# controller_power.net
KiCad netlist of a schematic drawn in Altium Designer
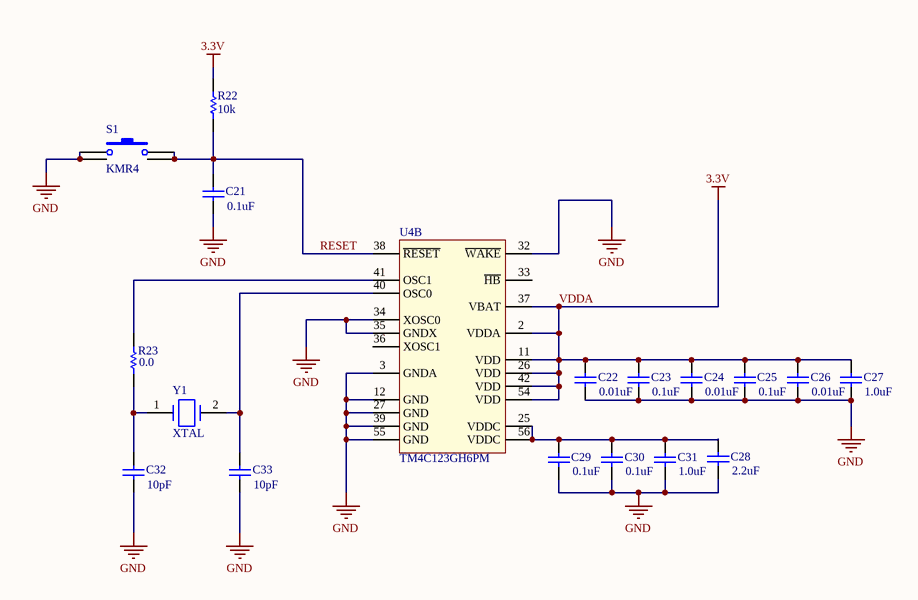
[diagram p0: controller_power.SchDoc]

(export (version "E")
  (design (tool "Eeschema 10.0.6"))
  (components
    (comp (ref "C21")
      (value "0.1uF")
      (footprint "1608[0603]")
      (description "Capacitor (Semiconductor SIM Model)")
      (fields (field (name "Comment") "Cap Semi") (field (name "PUBLISHER") "Altium Limited"))
      (libsource (lib "Miscellaneous Devices") (part "Cap Semi"))
    )
    (comp (ref "C22")
      (value "0.01uF")
      (footprint "1608[0603]")
      (description "Capacitor (Semiconductor SIM Model)")
      (fields (field (name "Comment") "Cap Semi") (field (name "PUBLISHER") "Altium Limited"))
      (libsource (lib "Miscellaneous Devices") (part "Cap Semi"))
    )
    (comp (ref "C23")
      (value "0.1uF")
      (footprint "1608[0603]")
      (description "Capacitor (Semiconductor SIM Model)")
      (fields (field (name "Comment") "Cap Semi") (field (name "PUBLISHER") "Altium Limited"))
      (libsource (lib "Miscellaneous Devices") (part "Cap Semi"))
    )
    (comp (ref "C24")
      (value "0.01uF")
      (footprint "1608[0603]")
      (description "Capacitor (Semiconductor SIM Model)")
      (fields (field (name "Comment") "Cap Semi") (field (name "PUBLISHER") "Altium Limited"))
      (libsource (lib "Miscellaneous Devices") (part "Cap Semi"))
    )
    (comp (ref "C25")
      (value "0.1uF")
      (footprint "1608[0603]")
      (description "Capacitor (Semiconductor SIM Model)")
      (fields (field (name "Comment") "Cap Semi") (field (name "PUBLISHER") "Altium Limited"))
      (libsource (lib "Miscellaneous Devices") (part "Cap Semi"))
    )
    (comp (ref "C26")
      (value "0.01uF")
      (footprint "1608[0603]")
      (description "Capacitor (Semiconductor SIM Model)")
      (fields (field (name "Comment") "Cap Semi") (field (name "PUBLISHER") "Altium Limited"))
      (libsource (lib "Miscellaneous Devices") (part "Cap Semi"))
    )
    (comp (ref "C27")
      (value "1.0uF")
      (footprint "1608[0603]")
      (description "Capacitor (Semiconductor SIM Model)")
      (fields (field (name "Comment") "Cap Semi") (field (name "PUBLISHER") "Altium Limited"))
      (libsource (lib "Miscellaneous Devices") (part "Cap Semi"))
    )
    (comp (ref "C28")
      (value "2.2uF")
      (footprint "1608[0603]")
      (description "Capacitor (Semiconductor SIM Model)")
      (fields (field (name "Comment") "Cap Semi") (field (name "PUBLISHER") "Altium Limited"))
      (libsource (lib "Miscellaneous Devices") (part "Cap Semi"))
    )
    (comp (ref "C29")
      (value "0.1uF")
      (footprint "1608[0603]")
      (description "Capacitor (Semiconductor SIM Model)")
      (fields (field (name "Comment") "Cap Semi") (field (name "PUBLISHER") "Altium Limited"))
      (libsource (lib "Miscellaneous Devices") (part "Cap Semi"))
    )
    (comp (ref "C30")
      (value "0.1uF")
      (footprint "1608[0603]")
      (description "Capacitor (Semiconductor SIM Model)")
      (fields (field (name "Comment") "Cap Semi") (field (name "PUBLISHER") "Altium Limited"))
      (libsource (lib "Miscellaneous Devices") (part "Cap Semi"))
    )
    (comp (ref "C31")
      (value "1.0uF")
      (footprint "1608[0603]")
      (description "Capacitor (Semiconductor SIM Model)")
      (fields (field (name "Comment") "Cap Semi") (field (name "PUBLISHER") "Altium Limited"))
      (libsource (lib "Miscellaneous Devices") (part "Cap Semi"))
    )
    (comp (ref "C32")
      (value "10pF")
      (footprint "1608[0603]")
      (description "Capacitor (Semiconductor SIM Model)")
      (fields (field (name "Comment") "Cap Semi") (field (name "PUBLISHER") "Altium Limited"))
      (libsource (lib "Miscellaneous Devices") (part "Cap Semi"))
    )
    (comp (ref "C33")
      (value "10pF")
      (footprint "1608[0603]")
      (description "Capacitor (Semiconductor SIM Model)")
      (fields (field (name "Comment") "Cap Semi") (field (name "PUBLISHER") "Altium Limited"))
      (libsource (lib "Miscellaneous Devices") (part "Cap Semi"))
    )
    (comp (ref "R22")
      (value "10k")
      (footprint "0603")
      (description "Resistor")
      (fields (field (name "PUBLISHER") "Altium Limited"))
      (libsource (lib "passives") (part "Resistor"))
    )
    (comp (ref "R23")
      (value "0.0")
      (footprint "0603")
      (description "Resistor")
      (fields (field (name "PUBLISHER") "Altium Limited"))
      (libsource (lib "passives") (part "Resistor"))
    )
    (comp (ref "S1")
      (value "KMR4")
      (footprint "KMR4")
      (description "Switch")
      (fields (field (name "PUBLISHER") "Altium Limited"))
      (libsource (lib "switches") (part "SPST Tactile Switch"))
    )
    (comp (ref "U4")
      (value "TM4C123GH6PM")
      (footprint "TSQFP50P1200X1200X145-64N")
      (description "Tiva C TM4C123GH6PM")
      (libsource (lib "microcontrollers") (part "TM4C123GH6PM"))
    )
    (comp (ref "Y1")
      (value "XTAL")
      (footprint "ABM3_SERIES")
      (description "Crystal Oscillator")
      (fields (field (name "PUBLISHER") "Altium Limited"))
      (libsource (lib "Devices") (part "XTAL"))
    )
  )
  (nets
    (net (code "1") (name "/RESET") (class "Default")
      (node (ref "C21") (pin "2") (pinfunction "2_2") (pintype "passive"))
      (node (ref "R22") (pin "1") (pinfunction "1_1") (pintype "passive"))
      (node (ref "S1") (pin "2") (pinfunction "2_2") (pintype "passive"))
      (node (ref "S1") (pin "4") (pinfunction "4_4") (pintype "passive"))
      (node (ref "U4") (pin "38") (pinfunction "~{RESET}_38") (pintype "passive"))
    )
    (net (code "2") (name "3.3V") (class "Default")
      (node (ref "C22") (pin "2") (pinfunction "2_2") (pintype "passive"))
      (node (ref "C23") (pin "2") (pinfunction "2_2") (pintype "passive"))
      (node (ref "C24") (pin "2") (pinfunction "2_2") (pintype "passive"))
      (node (ref "C25") (pin "2") (pinfunction "2_2") (pintype "passive"))
      (node (ref "C26") (pin "2") (pinfunction "2_2") (pintype "passive"))
      (node (ref "C27") (pin "2") (pinfunction "2_2") (pintype "passive"))
      (node (ref "R22") (pin "2") (pinfunction "2_2") (pintype "passive"))
      (node (ref "U4") (pin "11") (pinfunction "VDD_11") (pintype "passive"))
      (node (ref "U4") (pin "2") (pinfunction "VDDA_2") (pintype "passive"))
      (node (ref "U4") (pin "26") (pinfunction "VDD_26") (pintype "passive"))
      (node (ref "U4") (pin "37") (pinfunction "VBAT_37") (pintype "passive"))
      (node (ref "U4") (pin "42") (pinfunction "VDD_42") (pintype "passive"))
      (node (ref "U4") (pin "54") (pinfunction "VDD_54") (pintype "passive"))
    )
    (net (code "3") (name "GND") (class "Default")
      (node (ref "C21") (pin "1") (pinfunction "1_1") (pintype "passive"))
      (node (ref "C22") (pin "1") (pinfunction "1_1") (pintype "passive"))
      (node (ref "C23") (pin "1") (pinfunction "1_1") (pintype "passive"))
      (node (ref "C24") (pin "1") (pinfunction "1_1") (pintype "passive"))
      (node (ref "C25") (pin "1") (pinfunction "1_1") (pintype "passive"))
      (node (ref "C26") (pin "1") (pinfunction "1_1") (pintype "passive"))
      (node (ref "C27") (pin "1") (pinfunction "1_1") (pintype "passive"))
      (node (ref "C28") (pin "1") (pinfunction "1_1") (pintype "passive"))
      (node (ref "C29") (pin "1") (pinfunction "1_1") (pintype "passive"))
      (node (ref "C30") (pin "1") (pinfunction "1_1") (pintype "passive"))
      (node (ref "C31") (pin "1") (pinfunction "1_1") (pintype "passive"))
      (node (ref "C32") (pin "1") (pinfunction "1_1") (pintype "passive"))
      (node (ref "C33") (pin "1") (pinfunction "1_1") (pintype "passive"))
      (node (ref "S1") (pin "1") (pinfunction "1_1") (pintype "passive"))
      (node (ref "S1") (pin "3") (pinfunction "3_3") (pintype "passive"))
      (node (ref "U4") (pin "12") (pinfunction "GND_12") (pintype "passive"))
      (node (ref "U4") (pin "27") (pinfunction "GND_27") (pintype "passive"))
      (node (ref "U4") (pin "3") (pinfunction "GNDA_3") (pintype "passive"))
      (node (ref "U4") (pin "32") (pinfunction "~{WAKE}_32") (pintype "passive"))
      (node (ref "U4") (pin "34") (pinfunction "XOSC0_34") (pintype "passive"))
      (node (ref "U4") (pin "35") (pinfunction "GNDX_35") (pintype "passive"))
      (node (ref "U4") (pin "39") (pinfunction "GND_39") (pintype "passive"))
      (node (ref "U4") (pin "55") (pinfunction "GND_55") (pintype "passive"))
    )
    (net (code "4") (name "Net-(C28-Pad2)") (class "Default")
      (node (ref "C28") (pin "2") (pinfunction "2_2") (pintype "passive"))
      (node (ref "C29") (pin "2") (pinfunction "2_2") (pintype "passive"))
      (node (ref "C30") (pin "2") (pinfunction "2_2") (pintype "passive"))
      (node (ref "C31") (pin "2") (pinfunction "2_2") (pintype "passive"))
      (node (ref "U4") (pin "25") (pinfunction "VDDC_25") (pintype "passive"))
      (node (ref "U4") (pin "56") (pinfunction "VDDC_56") (pintype "passive"))
    )
    (net (code "5") (name "Net-(U4B-OSC0)") (class "Default")
      (node (ref "C33") (pin "2") (pinfunction "2_2") (pintype "passive"))
      (node (ref "U4") (pin "40") (pinfunction "OSC0_40") (pintype "passive"))
      (node (ref "Y1") (pin "2") (pinfunction "OSC2_2") (pintype "passive"))
    )
    (net (code "6") (name "Net-(U4B-OSC1)") (class "Default")
      (node (ref "R23") (pin "2") (pinfunction "2_2") (pintype "passive"))
      (node (ref "U4") (pin "41") (pinfunction "OSC1_41") (pintype "passive"))
    )
    (net (code "7") (name "Net-(Y1-OSC1)") (class "Default")
      (node (ref "C32") (pin "2") (pinfunction "2_2") (pintype "passive"))
      (node (ref "R23") (pin "1") (pinfunction "1_1") (pintype "passive"))
      (node (ref "Y1") (pin "1") (pinfunction "OSC1_1") (pintype "passive"))
    )
    (net (code "8") (name "unconnected-(U4B-XOSC1-Pad36)") (class "Default")
      (node (ref "U4") (pin "36") (pinfunction "XOSC1_36") (pintype "passive"))
    )
    (net (code "9") (name "unconnected-(U4B-~{HB}-Pad33)") (class "Default")
      (node (ref "U4") (pin "33") (pinfunction "~{HB}_33") (pintype "passive"))
    )
  )
)
